# rangkaian.net
KiCad netlist of a schematic drawn in EAGLE
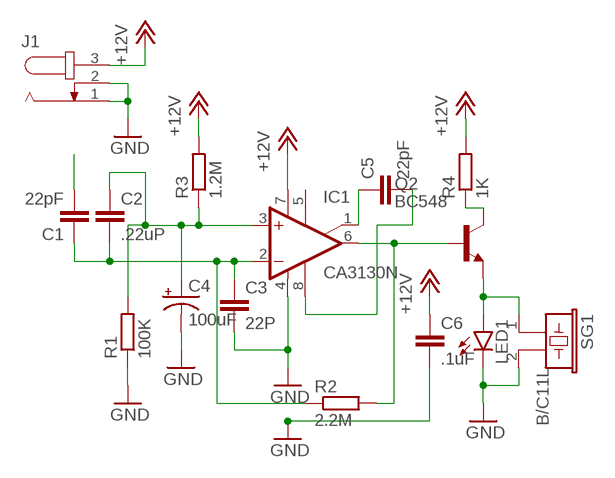
[diagram p0: schematic, sheet 1]

(export (version "E")
  (design (tool "Eeschema 10.0.6"))
  (components
    (comp (ref "C1")
      (value "22pF")
      (footprint "eagle-import:C025-025X050")
      (libsource (lib "eagle-import") (part "C-EU025-025X050"))
    )
    (comp (ref "C2")
      (value ".22uP")
      (footprint "eagle-import:C025-025X050")
      (libsource (lib "eagle-import") (part "C-EU025-025X050"))
    )
    (comp (ref "C3")
      (value "22P")
      (footprint "eagle-import:C025-025X050")
      (libsource (lib "eagle-import") (part "C-EU025-025X050"))
    )
    (comp (ref "C4")
      (value "100uF")
      (footprint "eagle-import:E3,5-8")
      (libsource (lib "eagle-import") (part "CPOL-USE3.5-8"))
    )
    (comp (ref "C5")
      (value "22pF")
      (footprint "eagle-import:C025-025X050")
      (libsource (lib "eagle-import") (part "C-EU025-025X050"))
    )
    (comp (ref "C6")
      (value ".1uF")
      (footprint "eagle-import:C025-025X050")
      (libsource (lib "eagle-import") (part "C-EU025-025X050"))
    )
    (comp (ref "IC1")
      (value "CA3130N")
      (footprint "eagle-import:DIL08")
      (libsource (lib "eagle-import") (part "CA3130N"))
    )
    (comp (ref "J1")
      (value "JACK-PLUG0")
      (footprint "eagle-import:SPC4077")
      (libsource (lib "eagle-import") (part "JACK-PLUG0"))
    )
    (comp (ref "LED1")
      (value "LED5MM")
      (footprint "eagle-import:LED5MM")
      (libsource (lib "eagle-import") (part "LED5MM"))
    )
    (comp (ref "Q2")
      (value "BC548")
      (footprint "eagle-import:TO92-EBC")
      (libsource (lib "eagle-import") (part "BC548"))
    )
    (comp (ref "R1")
      (value "100K")
      (footprint "eagle-import:0204_7")
      (libsource (lib "eagle-import") (part "R-EU_0204/7"))
    )
    (comp (ref "R2")
      (value "2.2M")
      (footprint "eagle-import:0204_7")
      (libsource (lib "eagle-import") (part "R-EU_0204/7"))
    )
    (comp (ref "R3")
      (value "1.2M")
      (footprint "eagle-import:0204_7")
      (libsource (lib "eagle-import") (part "R-EU_0204/7"))
    )
    (comp (ref "R4")
      (value "1K")
      (footprint "eagle-import:0204_7")
      (libsource (lib "eagle-import") (part "R-EU_0204/7"))
    )
    (comp (ref "SG1")
      (value "B/C11L")
      (footprint "eagle-import:B_C11L")
      (libsource (lib "eagle-import") (part "B/C11L"))
    )
  )
  (nets
    (net (code "1") (name "+12V") (class "Default")
      (node (ref "C6") (pin "1") (pinfunction "1_1") (pintype "passive"))
      (node (ref "IC1") (pin "7") (pinfunction "V+_7") (pintype "power_in"))
      (node (ref "J1") (pin "3") (pinfunction "3_3") (pintype "passive"))
      (node (ref "R3") (pin "2") (pinfunction "2_2") (pintype "passive"))
      (node (ref "R4") (pin "2") (pinfunction "2_2") (pintype "passive"))
    )
    (net (code "2") (name "GND") (class "Default")
      (node (ref "C3") (pin "2") (pinfunction "2_2") (pintype "passive"))
      (node (ref "C4") (pin "-") (pinfunction "-_-") (pintype "passive"))
      (node (ref "C6") (pin "2") (pinfunction "2_2") (pintype "passive"))
      (node (ref "IC1") (pin "4") (pinfunction "V-_4") (pintype "power_in"))
      (node (ref "J1") (pin "1") (pinfunction "1_1") (pintype "passive"))
      (node (ref "J1") (pin "2") (pinfunction "2_2") (pintype "passive"))
      (node (ref "LED1") (pin "K") (pinfunction "C_K") (pintype "passive"))
      (node (ref "R1") (pin "1") (pinfunction "1_1") (pintype "passive"))
      (node (ref "SG1") (pin "2") (pinfunction "2_2") (pintype "passive"))
    )
    (net (code "3") (name "Net-(IC1-+IN)") (class "Default")
      (node (ref "C2") (pin "1") (pinfunction "1_1") (pintype "passive"))
      (node (ref "C4") (pin "+") (pinfunction "+_+") (pintype "passive"))
      (node (ref "IC1") (pin "3") (pinfunction "+IN_3") (pintype "input"))
      (node (ref "R1") (pin "2") (pinfunction "2_2") (pintype "passive"))
      (node (ref "R3") (pin "1") (pinfunction "1_1") (pintype "passive"))
    )
    (net (code "4") (name "Net-(IC1--IN)") (class "Default")
      (node (ref "C1") (pin "1") (pinfunction "1_1") (pintype "passive"))
      (node (ref "C2") (pin "2") (pinfunction "2_2") (pintype "passive"))
      (node (ref "C3") (pin "1") (pinfunction "1_1") (pintype "passive"))
      (node (ref "IC1") (pin "2") (pinfunction "-IN_2") (pintype "input"))
      (node (ref "R2") (pin "1") (pinfunction "1_1") (pintype "passive"))
    )
    (net (code "5") (name "Net-(IC1-CMP)") (class "Default")
      (node (ref "C5") (pin "2") (pinfunction "2_2") (pintype "passive"))
      (node (ref "IC1") (pin "8") (pinfunction "CMP_8") (pintype "passive"))
    )
    (net (code "6") (name "Net-(IC1-ON{slash}CMP)") (class "Default")
      (node (ref "C5") (pin "1") (pinfunction "1_1") (pintype "passive"))
      (node (ref "IC1") (pin "1") (pinfunction "ON/CMP_1") (pintype "passive"))
    )
    (net (code "7") (name "Net-(IC1-OUT)") (class "Default")
      (node (ref "IC1") (pin "6") (pinfunction "OUT_6") (pintype "output"))
      (node (ref "Q2") (pin "B") (pinfunction "B_B") (pintype "passive"))
      (node (ref "R2") (pin "2") (pinfunction "2_2") (pintype "passive"))
    )
    (net (code "8") (name "Net-(LED1-PadA)") (class "Default")
      (node (ref "LED1") (pin "A") (pinfunction "A_A") (pintype "passive"))
      (node (ref "Q2") (pin "E") (pinfunction "E_E") (pintype "passive"))
      (node (ref "SG1") (pin "1") (pinfunction "1_1") (pintype "passive"))
    )
    (net (code "9") (name "Net-(Q2-PadC)") (class "Default")
      (node (ref "Q2") (pin "C") (pinfunction "C_C") (pintype "passive"))
      (node (ref "R4") (pin "1") (pinfunction "1_1") (pintype "passive"))
    )
    (net (code "10") (name "unconnected-(C1-Pad2)") (class "Default")
      (node (ref "C1") (pin "2") (pinfunction "2_2") (pintype "passive"))
    )
    (net (code "11") (name "unconnected-(IC1-ON-Pad5)") (class "Default")
      (node (ref "IC1") (pin "5") (pinfunction "ON_5") (pintype "passive"))
    )
  )
)
